# ftdi232h.net
KiCad netlist of a schematic drawn in Altium Designer
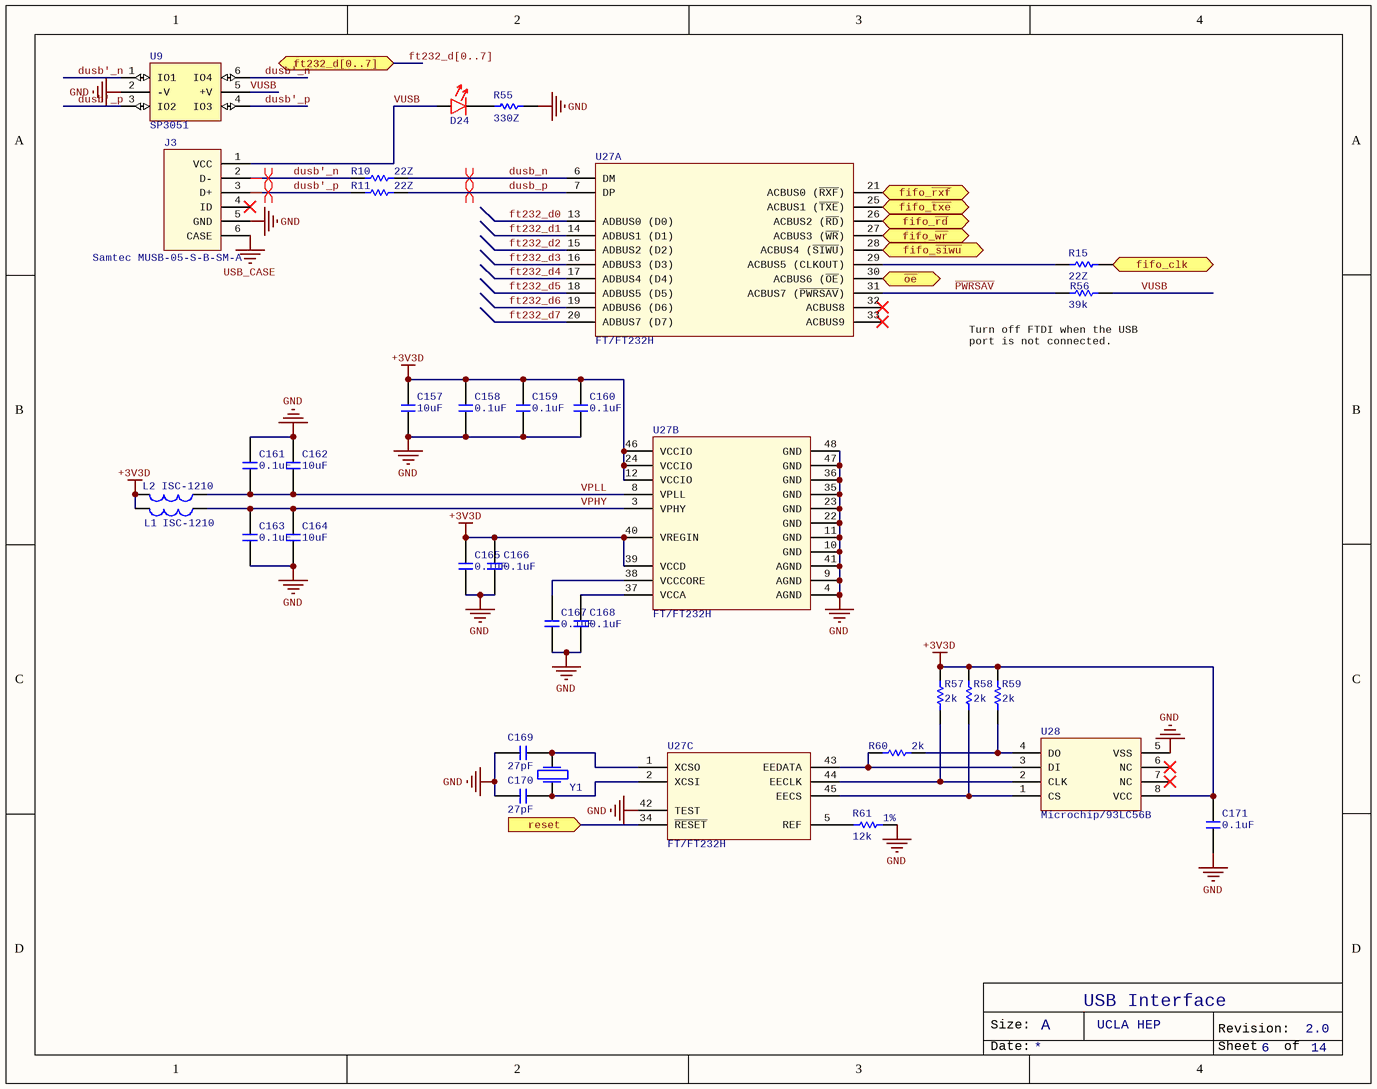
[diagram p0: ftdi232h.SchDoc]

(export (version "E")
  (design (tool "Eeschema 10.0.6"))
  (components
    (comp (ref "C157")
      (value "10uF")
      (footprint "c1206")
      (description "CAP2, CER, 10uF, 10%, 35V, 1206")
      (fields
        (field (name "MANUFACTURER") "Taiyo Yuden")
        (field (name "MANUFACTURER PART NUMBER") "GMK316F106ZL-T")
      )
      (libsource (lib "stdlib") (part "CAP/GMK316F106ZL-T"))
    )
    (comp (ref "C158")
      (value "0.1uF")
      (footprint "C0402")
      (description "CAP2, CER, 0.1uF, 10%, 25V, 0402, X5R")
      (fields
        (field (name "MANUFACTURER") "Murata Electronics North America")
        (field (name "MANUFACTURER PART NUMBER") "GRM155R61E104KA87D")
      )
      (libsource (lib "stdlib") (part "CAP/GRM155R61E104KA87D"))
    )
    (comp (ref "C159")
      (value "0.1uF")
      (footprint "C0402")
      (description "CAP2, CER, 0.1uF, 10%, 25V, 0402, X5R")
      (fields
        (field (name "MANUFACTURER") "Murata Electronics North America")
        (field (name "MANUFACTURER PART NUMBER") "GRM155R61E104KA87D")
      )
      (libsource (lib "stdlib") (part "CAP/GRM155R61E104KA87D"))
    )
    (comp (ref "C160")
      (value "0.1uF")
      (footprint "C0402")
      (description "CAP2, CER, 0.1uF, 10%, 25V, 0402, X5R")
      (fields
        (field (name "MANUFACTURER") "Murata Electronics North America")
        (field (name "MANUFACTURER PART NUMBER") "GRM155R61E104KA87D")
      )
      (libsource (lib "stdlib") (part "CAP/GRM155R61E104KA87D"))
    )
    (comp (ref "C161")
      (value "0.1uF")
      (footprint "C0402")
      (description "CAP2, CER, 0.1uF, 10%, 25V, 0402, X5R")
      (fields
        (field (name "MANUFACTURER") "Murata Electronics North America")
        (field (name "MANUFACTURER PART NUMBER") "GRM155R61E104KA87D")
      )
      (libsource (lib "stdlib") (part "CAP/GRM155R61E104KA87D"))
    )
    (comp (ref "C162")
      (value "10uF")
      (footprint "c1206")
      (description "CAP2, CER, 10uF, 10%, 35V, 1206")
      (fields
        (field (name "MANUFACTURER") "Taiyo Yuden")
        (field (name "MANUFACTURER PART NUMBER") "GMK316F106ZL-T")
      )
      (libsource (lib "stdlib") (part "CAP/GMK316F106ZL-T"))
    )
    (comp (ref "C163")
      (value "0.1uF")
      (footprint "C0402")
      (description "CAP2, CER, 0.1uF, 10%, 25V, 0402, X5R")
      (fields
        (field (name "MANUFACTURER") "Murata Electronics North America")
        (field (name "MANUFACTURER PART NUMBER") "GRM155R61E104KA87D")
      )
      (libsource (lib "stdlib") (part "CAP/GRM155R61E104KA87D"))
    )
    (comp (ref "C164")
      (value "10uF")
      (footprint "c1206")
      (description "CAP2, CER, 10uF, 10%, 35V, 1206")
      (fields
        (field (name "MANUFACTURER") "Taiyo Yuden")
        (field (name "MANUFACTURER PART NUMBER") "GMK316F106ZL-T")
      )
      (libsource (lib "stdlib") (part "CAP/GMK316F106ZL-T"))
    )
    (comp (ref "C165")
      (value "0.1uF")
      (footprint "C0402")
      (description "CAP2, CER, 0.1uF, 10%, 25V, 0402, X5R")
      (fields
        (field (name "MANUFACTURER") "Murata Electronics North America")
        (field (name "MANUFACTURER PART NUMBER") "GRM155R61E104KA87D")
      )
      (libsource (lib "stdlib") (part "CAP/GRM155R61E104KA87D"))
    )
    (comp (ref "C166")
      (value "0.1uF")
      (footprint "C0402")
      (description "CAP2, CER, 0.1uF, 10%, 25V, 0402, X5R")
      (fields
        (field (name "MANUFACTURER") "Murata Electronics North America")
        (field (name "MANUFACTURER PART NUMBER") "GRM155R61E104KA87D")
      )
      (libsource (lib "stdlib") (part "CAP/GRM155R61E104KA87D"))
    )
    (comp (ref "C167")
      (value "0.1uF")
      (footprint "C0402")
      (description "CAP2, CER, 0.1uF, 10%, 25V, 0402, X5R")
      (fields
        (field (name "MANUFACTURER") "Murata Electronics North America")
        (field (name "MANUFACTURER PART NUMBER") "GRM155R61E104KA87D")
      )
      (libsource (lib "stdlib") (part "CAP/GRM155R61E104KA87D"))
    )
    (comp (ref "C168")
      (value "0.1uF")
      (footprint "C0402")
      (description "CAP2, CER, 0.1uF, 10%, 25V, 0402, X5R")
      (fields
        (field (name "MANUFACTURER") "Murata Electronics North America")
        (field (name "MANUFACTURER PART NUMBER") "GRM155R61E104KA87D")
      )
      (libsource (lib "stdlib") (part "CAP/GRM155R61E104KA87D"))
    )
    (comp (ref "C169")
      (value "27pF")
      (footprint "C0402")
      (fields
        (field (name "MANUFACTURER") "Kemet")
        (field (name "MANUFACTURER PART NUMBER") "C0402C270F5GACTU")
        (field (name "TOLERANCE") "±1%")
      )
      (libsource (lib "tester_board") (part "CAP CER 27PF 50V 1% NP0 0402"))
    )
    (comp (ref "C170")
      (value "27pF")
      (footprint "C0402")
      (fields
        (field (name "MANUFACTURER") "Kemet")
        (field (name "MANUFACTURER PART NUMBER") "C0402C270F5GACTU")
        (field (name "TOLERANCE") "±1%")
      )
      (libsource (lib "tester_board") (part "CAP CER 27PF 50V 1% NP0 0402"))
    )
    (comp (ref "C171")
      (value "0.1uF")
      (footprint "C0402")
      (description "CAP2, CER, 0.1uF, 10%, 25V, 0402, X5R")
      (fields
        (field (name "MANUFACTURER") "Murata Electronics North America")
        (field (name "MANUFACTURER PART NUMBER") "GRM155R61E104KA87D")
      )
      (libsource (lib "stdlib") (part "CAP/GRM155R61E104KA87D"))
    )
    (comp (ref "D24")
      (value "LITEON/LTST-C171KRKT")
      (footprint "LED0805")
      (description "LED, 20mA, 0805, Red")
      (libsource (lib "stdlib") (part "LITEON/LTST-C171KRKT"))
    )
    (comp (ref "J3")
      (value "Samtec MUSB-05-S-B-SM-A")
      (footprint "MUSB-05-S-B-SM-A")
      (description "USB, Mini-USB, SMD")
      (fields
        (field (name "MANUFACTURER") "Samtec Inc.")
        (field (name "MANUFACTURER PART NUMBER") "MUSB-05-S-B-SM-A")
      )
      (libsource (lib "stdlib") (part "Samtec/MUSB-05-S-B-SM-A"))
    )
    (comp (ref "L1")
      (value "ISC-1210")
      (footprint "ISC-1210")
      (description "IND, 86uF, 90mA")
      (libsource (lib "stdlib") (part "ISC-1210"))
    )
    (comp (ref "L2")
      (value "ISC-1210")
      (footprint "ISC-1210")
      (description "IND, 86uF, 90mA")
      (libsource (lib "stdlib") (part "ISC-1210"))
    )
    (comp (ref "R10")
      (value "22Z")
      (footprint "R0402")
      (description "RES0, SMD, 22.0Z, 1.0%, 1/16W, 0402")
      (fields
        (field (name "MANUFACTURER") "Yageo")
        (field (name "MANUFACTURER PART NUMBER") "RC0402FR-0722RL")
      )
      (libsource (lib "stdlib") (part "RES/ 311-22.0LRCT-ND"))
    )
    (comp (ref "R11")
      (value "22Z")
      (footprint "R0402")
      (description "RES0, SMD, 22.0Z, 1.0%, 1/16W, 0402")
      (fields
        (field (name "MANUFACTURER") "Yageo")
        (field (name "MANUFACTURER PART NUMBER") "RC0402FR-0722RL")
      )
      (libsource (lib "stdlib") (part "RES/ 311-22.0LRCT-ND"))
    )
    (comp (ref "R15")
      (value "22Z")
      (footprint "R0603")
      (description "RES0, SMD, 22.0Z, 1.0%, 1/10W, 0603")
      (fields
        (field (name "MANUFACTURER") "Rohm Semiconductor")
        (field (name "MANUFACTURER PART NUMBER") "MCR03ERTF22R0")
      )
      (libsource (lib "stdlib") (part "CRCW060322R0FKEA"))
    )
    (comp (ref "R55")
      (value "330Z")
      (footprint "R0603")
      (description "RES0, SMD,  330Z, 1.0%, 1/10W, 0603")
      (fields
        (field (name "MANUFACTURER") "Rohm Semiconductor")
        (field (name "MANUFACTURER PART NUMBER") "MCR03ERTF3300")
      )
      (libsource (lib "stdlib") (part "CRCW0603330RFKEA"))
    )
    (comp (ref "R56")
      (value "39k")
      (footprint "R0603")
      (description "RES1, SMD, 39.0k, 1.0%, 1/10W, 0603")
      (libsource (lib "stdlib") (part "CRCW060339K0FKEA"))
    )
    (comp (ref "R57")
      (value "2k")
      (footprint "R0603")
      (description "RES1, SMD, 2.00k, 1.0%, 1/10W, 0603")
      (libsource (lib "stdlib") (part "CRCW06032K00FKEA"))
    )
    (comp (ref "R58")
      (value "2k")
      (footprint "R0603")
      (description "RES1, SMD, 2.00k, 1.0%, 1/10W, 0603")
      (libsource (lib "stdlib") (part "CRCW06032K00FKEA"))
    )
    (comp (ref "R59")
      (value "2k")
      (footprint "R0603")
      (description "RES1, SMD, 2.00k, 1.0%, 1/10W, 0603")
      (libsource (lib "stdlib") (part "CRCW06032K00FKEA"))
    )
    (comp (ref "R60")
      (value "2k")
      (footprint "R0603")
      (description "RES1, SMD, 2.00k, 1.0%, 1/10W, 0603")
      (libsource (lib "stdlib") (part "CRCW06032K00FKEA"))
    )
    (comp (ref "R61")
      (value "12k")
      (footprint "R0603")
      (description "RES1, SMD, 12.0k, 1.0%, 1/10W, 0603")
      (libsource (lib "stdlib") (part "CRCW060312K0FKEA"))
    )
    (comp (ref "U9")
      (value "SP3051")
      (footprint "SOT23-6")
      (description "TVS, 6VWM, 16VC")
      (fields
        (field (name "MANUFACTURER") "Littelfuse Inc.")
        (field (name "MANUFACTURER PART NUMBER") "SP3051-04HTG")
      )
      (libsource (lib "stdlib") (part "Littelfuse/SP3051-04HTG"))
    )
    (comp (ref "U27")
      (value "FT/FT232H")
      (footprint "LQFP-48")
      (description "FTDI 232H USB-UART")
      (libsource (lib "stdlib") (part "FT/FT232H"))
    )
    (comp (ref "U28")
      (value "Microchip/93LC56B")
      (footprint "SOIC-8")
      (description "EEPROM, 2Kb, 16-bitwidth")
      (fields
        (field (name "MANUFACTURER") "Microchip Technology")
        (field (name "MANUFACTURER PART NUMBER") "93LC56B-I/SN")
      )
      (libsource (lib "stdlib") (part "Microchip/93LC56B"))
    )
    (comp (ref "Y1")
      (value "XTAL")
      (footprint "XTAL")
      (description "XT9S20ANA16M")
      (fields (field (name "MANUFACTURER") "VISHAY DALE"))
      (libsource (lib "tester_board") (part "XTAL"))
    )
  )
  (nets
    (net (code "1") (name "+3V3D") (class "Default")
      (node (ref "C157") (pin "2") (pinfunction "2_2") (pintype "passive"))
      (node (ref "C158") (pin "2") (pinfunction "2_2") (pintype "passive"))
      (node (ref "C159") (pin "2") (pinfunction "2_2") (pintype "passive"))
      (node (ref "C160") (pin "2") (pinfunction "2_2") (pintype "passive"))
      (node (ref "C165") (pin "2") (pinfunction "2_2") (pintype "passive"))
      (node (ref "C166") (pin "2") (pinfunction "2_2") (pintype "passive"))
      (node (ref "C171") (pin "2") (pinfunction "2_2") (pintype "passive"))
      (node (ref "L1") (pin "1") (pintype "passive"))
      (node (ref "L2") (pin "1") (pintype "passive"))
      (node (ref "R57") (pin "2") (pinfunction "2_2") (pintype "passive"))
      (node (ref "R58") (pin "2") (pinfunction "2_2") (pintype "passive"))
      (node (ref "R59") (pin "2") (pinfunction "2_2") (pintype "passive"))
      (node (ref "U27") (pin "12") (pinfunction "VCCIO_12") (pintype "passive"))
      (node (ref "U27") (pin "24") (pinfunction "VCCIO_24") (pintype "passive"))
      (node (ref "U27") (pin "39") (pinfunction "VCCD_39") (pintype "passive"))
      (node (ref "U27") (pin "40") (pinfunction "VREGIN_40") (pintype "passive"))
      (node (ref "U27") (pin "46") (pinfunction "VCCIO_46") (pintype "passive"))
      (node (ref "U28") (pin "8") (pinfunction "VCC_8") (pintype "passive"))
    )
    (net (code "2") (name "/VPHY") (class "Default")
      (node (ref "C163") (pin "2") (pinfunction "2_2") (pintype "passive"))
      (node (ref "C164") (pin "1") (pinfunction "5_1") (pintype "passive"))
      (node (ref "L1") (pin "2") (pintype "passive"))
      (node (ref "U27") (pin "3") (pinfunction "VPHY_3") (pintype "passive"))
    )
    (net (code "3") (name "/VPLL") (class "Default")
      (node (ref "C161") (pin "1") (pinfunction "5_1") (pintype "passive"))
      (node (ref "C162") (pin "1") (pinfunction "5_1") (pintype "passive"))
      (node (ref "L2") (pin "2") (pintype "passive"))
      (node (ref "U27") (pin "8") (pinfunction "VPLL_8") (pintype "passive"))
    )
    (net (code "4") (name "/VUSB") (class "Default")
      (node (ref "D24") (pin "A") (pintype "passive"))
      (node (ref "J3") (pin "1") (pinfunction "VCC_1") (pintype "passive"))
      (node (ref "R56") (pin "2") (pinfunction "2_2") (pintype "passive"))
      (node (ref "U9") (pin "5") (pinfunction "+V_5") (pintype "power_in"))
    )
    (net (code "5") (name "/dusb'_n") (class "Default")
      (node (ref "J3") (pin "2") (pinfunction "D-_2") (pintype "passive"))
      (node (ref "R10") (pin "1") (pinfunction "1_1") (pintype "passive"))
      (node (ref "U9") (pin "1") (pinfunction "IO1_1") (pintype "bidirectional"))
      (node (ref "U9") (pin "6") (pinfunction "IO4_6") (pintype "bidirectional"))
    )
    (net (code "6") (name "/dusb'_p") (class "Default")
      (node (ref "J3") (pin "3") (pinfunction "D+_3") (pintype "passive"))
      (node (ref "R11") (pin "1") (pinfunction "1_1") (pintype "passive"))
      (node (ref "U9") (pin "3") (pinfunction "IO2_3") (pintype "bidirectional"))
      (node (ref "U9") (pin "4") (pinfunction "IO3_4") (pintype "bidirectional"))
    )
    (net (code "7") (name "/dusb_n") (class "Default")
      (node (ref "R10") (pin "2") (pinfunction "2_2") (pintype "passive"))
      (node (ref "U27") (pin "6") (pinfunction "DM_6") (pintype "passive"))
    )
    (net (code "8") (name "/dusb_p") (class "Default")
      (node (ref "R11") (pin "2") (pinfunction "2_2") (pintype "passive"))
      (node (ref "U27") (pin "7") (pinfunction "DP_7") (pintype "passive"))
    )
    (net (code "9") (name "/fifo_clk") (class "Default")
      (node (ref "R15") (pin "2") (pinfunction "2_2") (pintype "passive"))
    )
    (net (code "10") (name "/fifo_~{rd}") (class "Default")
      (node (ref "U27") (pin "26") (pinfunction "ACBUS2_(~{RD})_26") (pintype "passive"))
    )
    (net (code "11") (name "/fifo_~{rxf}") (class "Default")
      (node (ref "U27") (pin "21") (pinfunction "ACBUS0_(~{RXF})_21") (pintype "passive"))
    )
    (net (code "12") (name "/fifo_~{siwu}") (class "Default")
      (node (ref "U27") (pin "28") (pinfunction "ACBUS4_(~{SIWU})_28") (pintype "passive"))
    )
    (net (code "13") (name "/fifo_~{txe}") (class "Default")
      (node (ref "U27") (pin "25") (pinfunction "ACBUS1_(~{TXE})_25") (pintype "passive"))
    )
    (net (code "14") (name "/fifo_~{wr}") (class "Default")
      (node (ref "U27") (pin "27") (pinfunction "ACBUS3_(~{WR})_27") (pintype "passive"))
    )
    (net (code "15") (name "/ft232_d0") (class "Default")
      (node (ref "U27") (pin "13") (pinfunction "ADBUS0_(D0)_13") (pintype "passive"))
    )
    (net (code "16") (name "/ft232_d1") (class "Default")
      (node (ref "U27") (pin "14") (pinfunction "ADBUS1_(D1)_14") (pintype "passive"))
    )
    (net (code "17") (name "/ft232_d2") (class "Default")
      (node (ref "U27") (pin "15") (pinfunction "ADBUS2_(D2)_15") (pintype "passive"))
    )
    (net (code "18") (name "/ft232_d3") (class "Default")
      (node (ref "U27") (pin "16") (pinfunction "ADBUS3_(D3)_16") (pintype "passive"))
    )
    (net (code "19") (name "/ft232_d4") (class "Default")
      (node (ref "U27") (pin "17") (pinfunction "ADBUS4_(D4)_17") (pintype "passive"))
    )
    (net (code "20") (name "/ft232_d5") (class "Default")
      (node (ref "U27") (pin "18") (pinfunction "ADBUS5_(D5)_18") (pintype "passive"))
    )
    (net (code "21") (name "/ft232_d6") (class "Default")
      (node (ref "U27") (pin "19") (pinfunction "ADBUS6_(D6)_19") (pintype "passive"))
    )
    (net (code "22") (name "/ft232_d7") (class "Default")
      (node (ref "U27") (pin "20") (pinfunction "ADBUS7_(D7)_20") (pintype "passive"))
    )
    (net (code "24") (name "/reset") (class "Default")
      (node (ref "U27") (pin "34") (pinfunction "~{RESET}_34") (pintype "passive"))
    )
    (net (code "25") (name "/~{PWRSAV}") (class "Default")
      (node (ref "R56") (pin "1") (pinfunction "1_1") (pintype "passive"))
      (node (ref "U27") (pin "31") (pinfunction "ACBUS7_(~{PWRSAV})_31") (pintype "passive"))
    )
    (net (code "26") (name "/~{oe}") (class "Default")
      (node (ref "U27") (pin "30") (pinfunction "ACBUS6_(~{OE})_30") (pintype "passive"))
    )
    (net (code "27") (name "GND") (class "Default")
      (node (ref "C157") (pin "1") (pinfunction "5_1") (pintype "passive"))
      (node (ref "C158") (pin "1") (pinfunction "5_1") (pintype "passive"))
      (node (ref "C159") (pin "1") (pinfunction "5_1") (pintype "passive"))
      (node (ref "C160") (pin "1") (pinfunction "5_1") (pintype "passive"))
      (node (ref "C161") (pin "2") (pinfunction "2_2") (pintype "passive"))
      (node (ref "C162") (pin "2") (pinfunction "2_2") (pintype "passive"))
      (node (ref "C163") (pin "1") (pinfunction "5_1") (pintype "passive"))
      (node (ref "C164") (pin "2") (pinfunction "2_2") (pintype "passive"))
      (node (ref "C165") (pin "1") (pinfunction "5_1") (pintype "passive"))
      (node (ref "C166") (pin "1") (pinfunction "5_1") (pintype "passive"))
      (node (ref "C167") (pin "1") (pinfunction "5_1") (pintype "passive"))
      (node (ref "C168") (pin "1") (pinfunction "5_1") (pintype "passive"))
      (node (ref "C169") (pin "2") (pinfunction "2_2") (pintype "passive"))
      (node (ref "C170") (pin "2") (pinfunction "2_2") (pintype "passive"))
      (node (ref "C171") (pin "1") (pinfunction "5_1") (pintype "passive"))
      (node (ref "J3") (pin "5") (pinfunction "GND_5") (pintype "passive"))
      (node (ref "R55") (pin "1") (pinfunction "1_1") (pintype "passive"))
      (node (ref "R61") (pin "2") (pinfunction "2_2") (pintype "passive"))
      (node (ref "U27") (pin "10") (pinfunction "GND_10") (pintype "passive"))
      (node (ref "U27") (pin "11") (pinfunction "GND_11") (pintype "passive"))
      (node (ref "U27") (pin "22") (pinfunction "GND_22") (pintype "passive"))
      (node (ref "U27") (pin "23") (pinfunction "GND_23") (pintype "passive"))
      (node (ref "U27") (pin "35") (pinfunction "GND_35") (pintype "passive"))
      (node (ref "U27") (pin "36") (pinfunction "GND_36") (pintype "passive"))
      (node (ref "U27") (pin "4") (pinfunction "AGND_4") (pintype "passive"))
      (node (ref "U27") (pin "41") (pinfunction "AGND_41") (pintype "passive"))
      (node (ref "U27") (pin "42") (pinfunction "TEST_42") (pintype "passive"))
      (node (ref "U27") (pin "47") (pinfunction "GND_47") (pintype "passive"))
      (node (ref "U27") (pin "48") (pinfunction "GND_48") (pintype "passive"))
      (node (ref "U27") (pin "9") (pinfunction "AGND_9") (pintype "passive"))
      (node (ref "U28") (pin "5") (pinfunction "VSS_5") (pintype "passive"))
      (node (ref "U9") (pin "2") (pinfunction "-V_2") (pintype "power_in"))
    )
    (net (code "28") (name "Net-(C169-5)") (class "Default")
      (node (ref "C169") (pin "1") (pinfunction "5_1") (pintype "passive"))
      (node (ref "U27") (pin "1") (pinfunction "XCSO_1") (pintype "passive"))
      (node (ref "Y1") (pin "2") (pinfunction "2_2") (pintype "passive"))
    )
    (net (code "29") (name "Net-(C170-5)") (class "Default")
      (node (ref "C170") (pin "1") (pinfunction "5_1") (pintype "passive"))
      (node (ref "U27") (pin "2") (pinfunction "XCSI_2") (pintype "passive"))
      (node (ref "Y1") (pin "1") (pinfunction "1_1") (pintype "passive"))
    )
    (net (code "30") (name "Net-(D24-PadC)") (class "Default")
      (node (ref "D24") (pin "C") (pintype "passive"))
      (node (ref "R55") (pin "2") (pinfunction "2_2") (pintype "passive"))
    )
    (net (code "31") (name "Net-(U27A-ACBUS5_(CLKOUT))") (class "Default")
      (node (ref "R15") (pin "1") (pinfunction "1_1") (pintype "passive"))
      (node (ref "U27") (pin "29") (pinfunction "ACBUS5_(CLKOUT)_29") (pintype "passive"))
    )
    (net (code "32") (name "Net-(U27B-VCCA)") (class "Default")
      (node (ref "C168") (pin "2") (pinfunction "2_2") (pintype "passive"))
      (node (ref "U27") (pin "37") (pinfunction "VCCA_37") (pintype "passive"))
    )
    (net (code "33") (name "Net-(U27B-VCCCORE)") (class "Default")
      (node (ref "C167") (pin "2") (pinfunction "2_2") (pintype "passive"))
      (node (ref "U27") (pin "38") (pinfunction "VCCCORE_38") (pintype "passive"))
    )
    (net (code "34") (name "Net-(U27C-EECLK)") (class "Default")
      (node (ref "R57") (pin "1") (pinfunction "1_1") (pintype "passive"))
      (node (ref "U27") (pin "44") (pinfunction "EECLK_44") (pintype "passive"))
      (node (ref "U28") (pin "2") (pinfunction "CLK_2") (pintype "passive"))
    )
    (net (code "35") (name "Net-(U27C-EECS)") (class "Default")
      (node (ref "R58") (pin "1") (pinfunction "1_1") (pintype "passive"))
      (node (ref "U27") (pin "45") (pinfunction "EECS_45") (pintype "passive"))
      (node (ref "U28") (pin "1") (pinfunction "CS_1") (pintype "passive"))
    )
    (net (code "36") (name "Net-(U27C-EEDATA)") (class "Default")
      (node (ref "R60") (pin "1") (pinfunction "1_1") (pintype "passive"))
      (node (ref "U27") (pin "43") (pinfunction "EEDATA_43") (pintype "passive"))
      (node (ref "U28") (pin "3") (pinfunction "DI_3") (pintype "passive"))
    )
    (net (code "37") (name "Net-(U27C-REF)") (class "Default")
      (node (ref "R61") (pin "1") (pinfunction "1_1") (pintype "passive"))
      (node (ref "U27") (pin "5") (pinfunction "REF_5") (pintype "passive"))
    )
    (net (code "38") (name "Net-(U28-DO)") (class "Default")
      (node (ref "R59") (pin "1") (pinfunction "1_1") (pintype "passive"))
      (node (ref "R60") (pin "2") (pinfunction "2_2") (pintype "passive"))
      (node (ref "U28") (pin "4") (pinfunction "DO_4") (pintype "passive"))
    )
    (net (code "39") (name "USB_CASE") (class "Default")
      (node (ref "J3") (pin "6") (pinfunction "CASE_6") (pintype "passive"))
    )
    (net (code "40") (name "unconnected-(J3-ID-Pad4)") (class "Default")
      (node (ref "J3") (pin "4") (pinfunction "ID_4") (pintype "passive+no_connect"))
    )
    (net (code "41") (name "unconnected-(U27A-ACBUS8-Pad32)") (class "Default")
      (node (ref "U27") (pin "32") (pinfunction "ACBUS8_32") (pintype "passive+no_connect"))
    )
    (net (code "42") (name "unconnected-(U27A-ACBUS9-Pad33)") (class "Default")
      (node (ref "U27") (pin "33") (pinfunction "ACBUS9_33") (pintype "passive+no_connect"))
    )
    (net (code "43") (name "unconnected-(U28-NC-Pad6)") (class "Default")
      (node (ref "U28") (pin "6") (pinfunction "NC_6") (pintype "passive+no_connect"))
    )
    (net (code "44") (name "unconnected-(U28-NC-Pad7)") (class "Default")
      (node (ref "U28") (pin "7") (pinfunction "NC_7") (pintype "passive+no_connect"))
    )
  )
)
